# programmer_shield.net
KiCad netlist of a schematic drawn in EAGLE
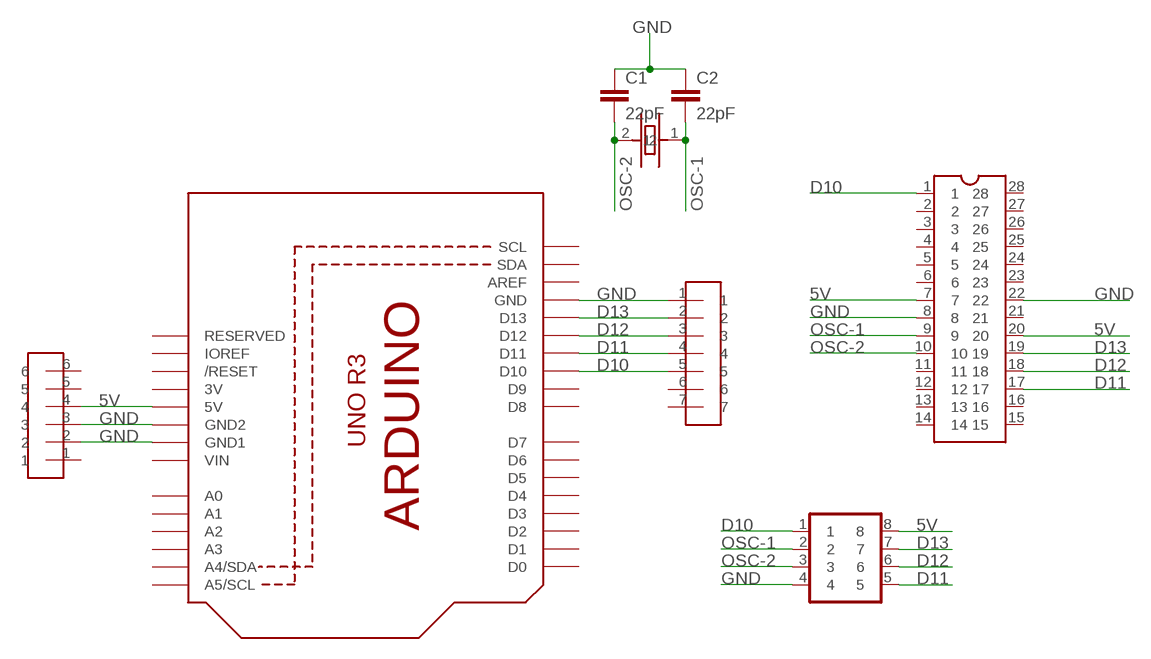
[diagram p0: schematic, sheet 1]

(export (version "E")
  (design (tool "Eeschema 10.0.6"))
  (components
    (comp (ref "C1")
      (value "22pF")
      (footprint "eagle-import:CAP-PTH-SMALL")
      (libsource (lib "eagle-import") (part "CAPPTH"))
    )
    (comp (ref "C2")
      (value "22pF")
      (footprint "eagle-import:CAP-PTH-SMALL")
      (libsource (lib "eagle-import") (part "CAPPTH"))
    )
    (comp (ref "U$1")
      (value "HEADER-6")
      (footprint "eagle-import:HEADER-6")
      (libsource (lib "eagle-import") (part "HEADER-6"))
    )
    (comp (ref "U$2")
      (value "HEADER-7")
      (footprint "eagle-import:HEADER-7")
      (libsource (lib "eagle-import") (part "HEADER-7"))
    )
    (comp (ref "U$3")
      (value "SOCKET-8PINDIP")
      (footprint "eagle-import:SOCKET-8PIN")
      (libsource (lib "eagle-import") (part "SOCKET-8PINDIP"))
    )
    (comp (ref "U$4")
      (value "16mhz")
      (footprint "eagle-import:CRYSTAL-DIP")
      (libsource (lib "eagle-import") (part "CRYSTAL16MHZ-DIP"))
    )
    (comp (ref "U$5")
      (value "SOCKET-28PIN")
      (footprint "eagle-import:SOCKET-28PIN")
      (libsource (lib "eagle-import") (part "SOCKET-28PIN"))
    )
    (comp (ref "U1")
      (value "ARDUINOR3-BPLACE")
      (footprint "eagle-import:ARDUINOR3-BPLACE")
      (libsource (lib "eagle-import") (part "ARDUINOR3-BPLACE"))
    )
  )
  (nets
    (net (code "1") (name "/3V") (class "Default")
      (node (ref "U1") (pin "3V") (pinfunction "3V_3V") (pintype "power_in"))
    )
    (net (code "2") (name "/5V") (class "Default")
      (node (ref "U$1") (pin "4") (pinfunction "4_4") (pintype "bidirectional"))
      (node (ref "U$3") (pin "8") (pinfunction "8_8") (pintype "bidirectional"))
      (node (ref "U$5") (pin "20") (pinfunction "20_20") (pintype "bidirectional"))
      (node (ref "U$5") (pin "7") (pinfunction "7_7") (pintype "bidirectional"))
      (node (ref "U1") (pin "5V") (pinfunction "5V_5V") (pintype "power_in"))
    )
    (net (code "3") (name "/D10") (class "Default")
      (node (ref "U$2") (pin "5") (pinfunction "5_5") (pintype "bidirectional"))
      (node (ref "U$3") (pin "1") (pinfunction "1_1") (pintype "bidirectional"))
      (node (ref "U$5") (pin "1") (pinfunction "1_1") (pintype "bidirectional"))
      (node (ref "U1") (pin "D10") (pinfunction "D10_D10") (pintype "bidirectional"))
    )
    (net (code "4") (name "/D11") (class "Default")
      (node (ref "U$2") (pin "4") (pinfunction "4_4") (pintype "bidirectional"))
      (node (ref "U$3") (pin "5") (pinfunction "5_5") (pintype "bidirectional"))
      (node (ref "U$5") (pin "17") (pinfunction "17_17") (pintype "bidirectional"))
      (node (ref "U1") (pin "D11") (pinfunction "D11_D11") (pintype "bidirectional"))
    )
    (net (code "5") (name "/D12") (class "Default")
      (node (ref "U$2") (pin "3") (pinfunction "3_3") (pintype "bidirectional"))
      (node (ref "U$3") (pin "6") (pinfunction "6_6") (pintype "bidirectional"))
      (node (ref "U$5") (pin "18") (pinfunction "18_18") (pintype "bidirectional"))
      (node (ref "U1") (pin "D12") (pinfunction "D12_D12") (pintype "bidirectional"))
    )
    (net (code "6") (name "/D13") (class "Default")
      (node (ref "U$2") (pin "2") (pinfunction "2_2") (pintype "bidirectional"))
      (node (ref "U$3") (pin "7") (pinfunction "7_7") (pintype "bidirectional"))
      (node (ref "U$5") (pin "19") (pinfunction "19_19") (pintype "bidirectional"))
      (node (ref "U1") (pin "D13") (pinfunction "D13_D13") (pintype "bidirectional"))
    )
    (net (code "7") (name "/GND") (class "Default")
      (node (ref "C1") (pin "1") (pinfunction "1_1") (pintype "passive"))
      (node (ref "C2") (pin "1") (pinfunction "1_1") (pintype "passive"))
      (node (ref "U$1") (pin "2") (pinfunction "2_2") (pintype "bidirectional"))
      (node (ref "U$1") (pin "3") (pinfunction "3_3") (pintype "bidirectional"))
      (node (ref "U$2") (pin "1") (pinfunction "1_1") (pintype "bidirectional"))
      (node (ref "U$3") (pin "4") (pinfunction "4_4") (pintype "bidirectional"))
      (node (ref "U$5") (pin "22") (pinfunction "22_22") (pintype "bidirectional"))
      (node (ref "U$5") (pin "8") (pinfunction "8_8") (pintype "bidirectional"))
      (node (ref "U1") (pin "GND") (pinfunction "GND_GND") (pintype "power_in"))
      (node (ref "U1") (pin "GND1") (pinfunction "GND1_GND1") (pintype "power_in"))
      (node (ref "U1") (pin "GND2") (pinfunction "GND2_GND2") (pintype "power_in"))
    )
    (net (code "8") (name "/OSC-1") (class "Default")
      (node (ref "C2") (pin "2") (pinfunction "2_2") (pintype "passive"))
      (node (ref "U$3") (pin "2") (pinfunction "2_2") (pintype "bidirectional"))
      (node (ref "U$4") (pin "1") (pinfunction "1_1") (pintype "bidirectional"))
      (node (ref "U$5") (pin "9") (pinfunction "9_9") (pintype "bidirectional"))
    )
    (net (code "9") (name "/OSC-2") (class "Default")
      (node (ref "C1") (pin "2") (pinfunction "2_2") (pintype "passive"))
      (node (ref "U$3") (pin "3") (pinfunction "3_3") (pintype "bidirectional"))
      (node (ref "U$4") (pin "2") (pinfunction "2_2") (pintype "bidirectional"))
      (node (ref "U$5") (pin "10") (pinfunction "10_10") (pintype "bidirectional"))
    )
    (net (code "10") (name "/VIN") (class "Default")
      (node (ref "U1") (pin "VIN") (pinfunction "VIN_VIN") (pintype "power_in"))
    )
    (net (code "11") (name "unconnected-(U$1-Pad1)") (class "Default")
      (node (ref "U$1") (pin "1") (pinfunction "1_1") (pintype "bidirectional"))
    )
    (net (code "12") (name "unconnected-(U$1-Pad5)") (class "Default")
      (node (ref "U$1") (pin "5") (pinfunction "5_5") (pintype "bidirectional"))
    )
    (net (code "13") (name "unconnected-(U$1-Pad6)") (class "Default")
      (node (ref "U$1") (pin "6") (pinfunction "6_6") (pintype "bidirectional"))
    )
    (net (code "14") (name "unconnected-(U$2-Pad6)") (class "Default")
      (node (ref "U$2") (pin "6") (pinfunction "6_6") (pintype "bidirectional"))
    )
    (net (code "15") (name "unconnected-(U$2-Pad7)") (class "Default")
      (node (ref "U$2") (pin "7") (pinfunction "7_7") (pintype "bidirectional"))
    )
    (net (code "16") (name "unconnected-(U$5-Pad2)") (class "Default")
      (node (ref "U$5") (pin "2") (pinfunction "2_2") (pintype "bidirectional"))
    )
    (net (code "17") (name "unconnected-(U$5-Pad3)") (class "Default")
      (node (ref "U$5") (pin "3") (pinfunction "3_3") (pintype "bidirectional"))
    )
    (net (code "18") (name "unconnected-(U$5-Pad4)") (class "Default")
      (node (ref "U$5") (pin "4") (pinfunction "4_4") (pintype "bidirectional"))
    )
    (net (code "19") (name "unconnected-(U$5-Pad5)") (class "Default")
      (node (ref "U$5") (pin "5") (pinfunction "5_5") (pintype "bidirectional"))
    )
    (net (code "20") (name "unconnected-(U$5-Pad6)") (class "Default")
      (node (ref "U$5") (pin "6") (pinfunction "6_6") (pintype "bidirectional"))
    )
    (net (code "21") (name "unconnected-(U$5-Pad11)") (class "Default")
      (node (ref "U$5") (pin "11") (pinfunction "11_11") (pintype "bidirectional"))
    )
    (net (code "22") (name "unconnected-(U$5-Pad12)") (class "Default")
      (node (ref "U$5") (pin "12") (pinfunction "12_12") (pintype "bidirectional"))
    )
    (net (code "23") (name "unconnected-(U$5-Pad13)") (class "Default")
      (node (ref "U$5") (pin "13") (pinfunction "13_13") (pintype "bidirectional"))
    )
    (net (code "24") (name "unconnected-(U$5-Pad14)") (class "Default")
      (node (ref "U$5") (pin "14") (pinfunction "14_14") (pintype "bidirectional"))
    )
    (net (code "25") (name "unconnected-(U$5-Pad15)") (class "Default")
      (node (ref "U$5") (pin "15") (pinfunction "15_15") (pintype "bidirectional"))
    )
    (net (code "26") (name "unconnected-(U$5-Pad16)") (class "Default")
      (node (ref "U$5") (pin "16") (pinfunction "16_16") (pintype "bidirectional"))
    )
    (net (code "27") (name "unconnected-(U$5-Pad21)") (class "Default")
      (node (ref "U$5") (pin "21") (pinfunction "21_21") (pintype "bidirectional"))
    )
    (net (code "28") (name "unconnected-(U$5-Pad23)") (class "Default")
      (node (ref "U$5") (pin "23") (pinfunction "23_23") (pintype "bidirectional"))
    )
    (net (code "29") (name "unconnected-(U$5-Pad24)") (class "Default")
      (node (ref "U$5") (pin "24") (pinfunction "24_24") (pintype "bidirectional"))
    )
    (net (code "30") (name "unconnected-(U$5-Pad25)") (class "Default")
      (node (ref "U$5") (pin "25") (pinfunction "25_25") (pintype "bidirectional"))
    )
    (net (code "31") (name "unconnected-(U$5-Pad26)") (class "Default")
      (node (ref "U$5") (pin "26") (pinfunction "26_26") (pintype "bidirectional"))
    )
    (net (code "32") (name "unconnected-(U$5-Pad27)") (class "Default")
      (node (ref "U$5") (pin "27") (pinfunction "27_27") (pintype "bidirectional"))
    )
    (net (code "33") (name "unconnected-(U$5-Pad28)") (class "Default")
      (node (ref "U$5") (pin "28") (pinfunction "28_28") (pintype "bidirectional"))
    )
    (net (code "34") (name "unconnected-(U1-A4{slash}SDA-PadA4)") (class "Default")
      (node (ref "U1") (pin "A4") (pinfunction "A4/SDA_A4") (pintype "bidirectional"))
    )
    (net (code "35") (name "unconnected-(U1-A5{slash}SCL-PadA5)") (class "Default")
      (node (ref "U1") (pin "A5") (pinfunction "A5/SCL_A5") (pintype "bidirectional"))
    )
    (net (code "36") (name "unconnected-(U1-PadA0)") (class "Default")
      (node (ref "U1") (pin "A0") (pinfunction "A0_A0") (pintype "bidirectional"))
    )
    (net (code "37") (name "unconnected-(U1-PadA1)") (class "Default")
      (node (ref "U1") (pin "A1") (pinfunction "A1_A1") (pintype "bidirectional"))
    )
    (net (code "38") (name "unconnected-(U1-PadA2)") (class "Default")
      (node (ref "U1") (pin "A2") (pinfunction "A2_A2") (pintype "bidirectional"))
    )
    (net (code "39") (name "unconnected-(U1-PadA3)") (class "Default")
      (node (ref "U1") (pin "A3") (pinfunction "A3_A3") (pintype "bidirectional"))
    )
    (net (code "40") (name "unconnected-(U1-PadAREF)") (class "Default")
      (node (ref "U1") (pin "AREF") (pinfunction "AREF_AREF") (pintype "bidirectional"))
    )
    (net (code "41") (name "unconnected-(U1-PadD0)") (class "Default")
      (node (ref "U1") (pin "D0") (pinfunction "D0_D0") (pintype "bidirectional"))
    )
    (net (code "42") (name "unconnected-(U1-PadD1)") (class "Default")
      (node (ref "U1") (pin "D1") (pinfunction "D1_D1") (pintype "bidirectional"))
    )
    (net (code "43") (name "unconnected-(U1-PadD2)") (class "Default")
      (node (ref "U1") (pin "D2") (pinfunction "D2_D2") (pintype "bidirectional"))
    )
    (net (code "44") (name "unconnected-(U1-PadD3)") (class "Default")
      (node (ref "U1") (pin "D3") (pinfunction "D3_D3") (pintype "bidirectional"))
    )
    (net (code "45") (name "unconnected-(U1-PadD4)") (class "Default")
      (node (ref "U1") (pin "D4") (pinfunction "D4_D4") (pintype "bidirectional"))
    )
    (net (code "46") (name "unconnected-(U1-PadD5)") (class "Default")
      (node (ref "U1") (pin "D5") (pinfunction "D5_D5") (pintype "bidirectional"))
    )
    (net (code "47") (name "unconnected-(U1-PadD6)") (class "Default")
      (node (ref "U1") (pin "D6") (pinfunction "D6_D6") (pintype "bidirectional"))
    )
    (net (code "48") (name "unconnected-(U1-PadD7)") (class "Default")
      (node (ref "U1") (pin "D7") (pinfunction "D7_D7") (pintype "bidirectional"))
    )
    (net (code "49") (name "unconnected-(U1-PadD8)") (class "Default")
      (node (ref "U1") (pin "D8") (pinfunction "D8_D8") (pintype "bidirectional"))
    )
    (net (code "50") (name "unconnected-(U1-PadD9)") (class "Default")
      (node (ref "U1") (pin "D9") (pinfunction "D9_D9") (pintype "bidirectional"))
    )
    (net (code "51") (name "unconnected-(U1-PadIOREF)") (class "Default")
      (node (ref "U1") (pin "IOREF") (pinfunction "IOREF_IOREF") (pintype "output"))
    )
    (net (code "52") (name "unconnected-(U1-PadRESERVED)") (class "Default")
      (node (ref "U1") (pin "RESERVED") (pinfunction "RESERVED_RESERVED") (pintype "no_connect"))
    )
    (net (code "53") (name "unconnected-(U1-PadSCL)") (class "Default")
      (node (ref "U1") (pin "SCL") (pinfunction "SCL_SCL") (pintype "bidirectional"))
    )
    (net (code "54") (name "unconnected-(U1-PadSDA)") (class "Default")
      (node (ref "U1") (pin "SDA") (pinfunction "SDA_SDA") (pintype "bidirectional"))
    )
    (net (code "55") (name "unconnected-(U1-{slash}RESET-PadRESET)") (class "Default")
      (node (ref "U1") (pin "RESET") (pinfunction "/RESET_RESET") (pintype "bidirectional"))
    )
  )
)
